# relay.net
KiCad netlist of a schematic drawn in Altium Designer
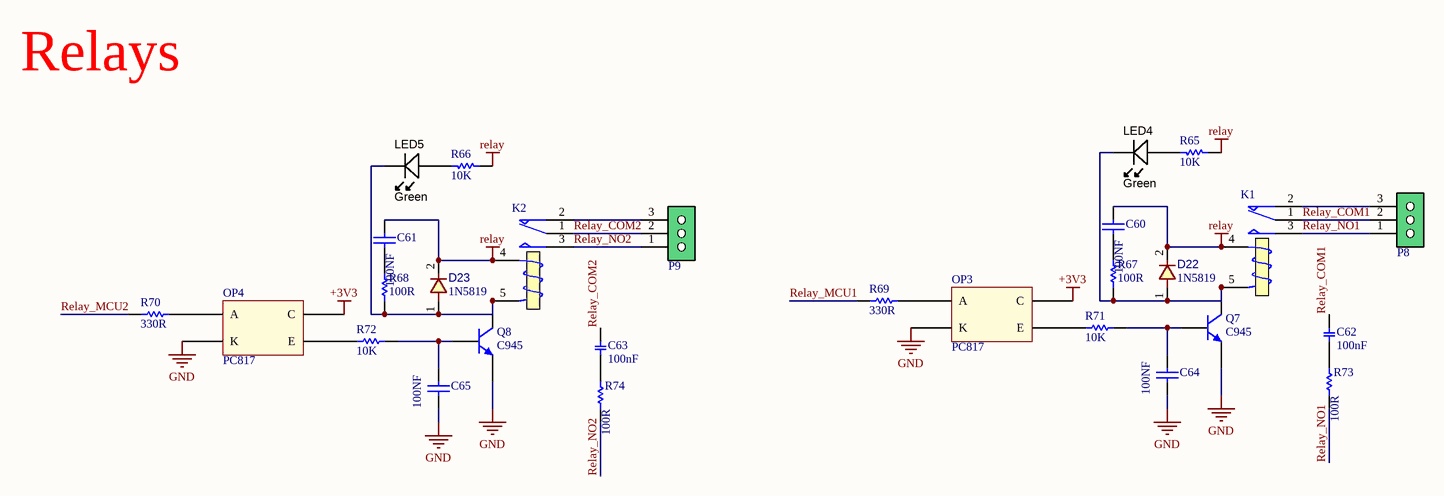
[diagram p0: relay.SchDoc]

(export (version "E")
  (design (tool "Eeschema 10.0.6"))
  (components
    (comp (ref "C60")
      (value "100NF")
      (footprint "CAP0603")
      (description "TOTAL CAPACITOR SMD PACK")
      (fields (field (name "DESIGNER") "Abbas Basereh"))
      (libsource (lib "Altium") (part "CAP SMD PACKAGE"))
    )
    (comp (ref "C61")
      (value "100NF")
      (footprint "CAP0603")
      (description "TOTAL CAPACITOR SMD PACK")
      (fields (field (name "DESIGNER") "Abbas Basereh"))
      (libsource (lib "Altium") (part "CAP SMD PACKAGE"))
    )
    (comp (ref "C62")
      (value "100nF")
      (footprint "Cap - 10nF - 630V")
      (description "Capacitor Polyester THD")
      (libsource (lib "Capacitor") (part "Capacitor Polyester THD"))
    )
    (comp (ref "C63")
      (value "100nF")
      (footprint "Cap - 10nF - 630V")
      (description "Capacitor Polyester THD")
      (libsource (lib "Capacitor") (part "Capacitor Polyester THD"))
    )
    (comp (ref "C64")
      (value "100NF")
      (footprint "CAP0603")
      (description "TOTAL CAPACITOR SMD PACK")
      (fields (field (name "DESIGNER") "Abbas Basereh"))
      (libsource (lib "Altium") (part "CAP SMD PACKAGE"))
    )
    (comp (ref "C65")
      (value "100NF")
      (footprint "CAP0603")
      (description "TOTAL CAPACITOR SMD PACK")
      (fields (field (name "DESIGNER") "Abbas Basereh"))
      (libsource (lib "Altium") (part "CAP SMD PACKAGE"))
    )
    (comp (ref "D22")
      (value "1N5819")
      (footprint "D_SMA")
      (description "DIODE, GENERAL PURPOSE, 1000V/1A")
      (fields (field (name "Comment") "1n5819 SMD SS31"))
      (libsource (lib "Diode") (part "1N4007 SMD M7"))
    )
    (comp (ref "D23")
      (value "1N5819")
      (footprint "D_SMA")
      (description "DIODE, GENERAL PURPOSE, 1000V/1A")
      (fields (field (name "Comment") "1n5819 SMD SS31"))
      (libsource (lib "Diode") (part "1N4007 SMD M7"))
    )
    (comp (ref "K1")
      (value "~")
      (footprint "Relay 18.85x15.35x15.70")
      (description "Single-Pole Dual-Throw Relay")
      (fields (field (name "DESIGNER") "Abbas Basereh"))
      (libsource (lib "2017AbbasBasereh9365731239 -ver1") (part "Relay_SPDT"))
    )
    (comp (ref "K2")
      (value "~")
      (footprint "Relay 18.85x15.35x15.70")
      (description "Single-Pole Dual-Throw Relay")
      (fields (field (name "DESIGNER") "Abbas Basereh"))
      (libsource (lib "2017AbbasBasereh9365731239 -ver1") (part "Relay_SPDT"))
    )
    (comp (ref "LED4")
      (value "Green")
      (footprint "LED-0603-GREEN")
      (description "LED 0603 SMD Green 570nm 50mcd 20mA")
      (libsource (lib "Utiliti_Library") (part "LED_SMD_Green_0603_570nm"))
    )
    (comp (ref "LED5")
      (value "Green")
      (footprint "LED-0603-GREEN")
      (description "LED 0603 SMD Green 570nm 50mcd 20mA")
      (libsource (lib "Utiliti_Library") (part "LED_SMD_Green_0603_570nm"))
    )
    (comp (ref "OP3")
      (value "PC817")
      (footprint "PC817 SMD")
      (description "PC817 optocpler")
      (libsource (lib "IC") (part "PC817"))
    )
    (comp (ref "OP4")
      (value "PC817")
      (footprint "PC817 SMD")
      (description "PC817 optocpler")
      (libsource (lib "IC") (part "PC817"))
    )
    (comp (ref "P8")
      (value "Phoenix 3")
      (footprint "PRKR3A")
      (libsource (lib "Connector") (part "Phoenix 3"))
    )
    (comp (ref "P9")
      (value "Phoenix 3")
      (footprint "PRKR3A")
      (libsource (lib "Connector") (part "Phoenix 3"))
    )
    (comp (ref "Q7")
      (value "C945")
      (footprint "SOT23_N")
      (description "NPN Silicon Epitaxial Planar Transistor")
      (fields (field (name "PUBLISHER") "Abbas Basereh"))
      (libsource (lib "2017AbbasBasereh9365731239 -ver1") (part "C945"))
    )
    (comp (ref "Q8")
      (value "C945")
      (footprint "SOT23_N")
      (description "NPN Silicon Epitaxial Planar Transistor")
      (fields (field (name "PUBLISHER") "Abbas Basereh"))
      (libsource (lib "2017AbbasBasereh9365731239 -ver1") (part "C945"))
    )
    (comp (ref "R65")
      (value "10K")
      (footprint "R0603")
      (description "Resistor SMD 0603")
      (libsource (lib "Resistor") (part "Resistor SMD 0603"))
    )
    (comp (ref "R66")
      (value "10K")
      (footprint "R0603")
      (description "Resistor SMD 0603")
      (libsource (lib "Resistor") (part "Resistor SMD 0603"))
    )
    (comp (ref "R67")
      (value "100R")
      (footprint "R0603")
      (description "Resistor SMD 0603")
      (libsource (lib "Resistor") (part "Resistor SMD 0603"))
    )
    (comp (ref "R68")
      (value "100R")
      (footprint "R0603")
      (description "Resistor SMD 0603")
      (libsource (lib "Resistor") (part "Resistor SMD 0603"))
    )
    (comp (ref "R69")
      (value "330R")
      (footprint "R0603")
      (description "Resistor SMD 0603")
      (libsource (lib "Resistor") (part "Resistor SMD 0603"))
    )
    (comp (ref "R70")
      (value "330R")
      (footprint "R0603")
      (description "Resistor SMD 0603")
      (libsource (lib "Resistor") (part "Resistor SMD 0603"))
    )
    (comp (ref "R71")
      (value "10K")
      (footprint "R0603")
      (description "Resistor SMD 0603")
      (libsource (lib "Resistor") (part "Resistor SMD 0603"))
    )
    (comp (ref "R72")
      (value "10K")
      (footprint "R0603")
      (description "Resistor SMD 0603")
      (libsource (lib "Resistor") (part "Resistor SMD 0603"))
    )
    (comp (ref "R73")
      (value "100R")
      (footprint "SMD-2512-RES")
      (description "Resistor SMD 2512")
      (libsource (lib "Resistor") (part "Resistor SMD 2512"))
    )
    (comp (ref "R74")
      (value "100R")
      (footprint "SMD-2512-RES")
      (description "Resistor SMD 2512")
      (libsource (lib "Resistor") (part "Resistor SMD 2512"))
    )
  )
  (nets
    (net (code "1") (name "+3V3") (class "Default")
      (node (ref "OP3") (pin "4") (pinfunction "C_4") (pintype "passive"))
      (node (ref "OP4") (pin "4") (pinfunction "C_4") (pintype "passive"))
    )
    (net (code "2") (name "/Relay_COM1") (class "Default")
      (node (ref "C62") (pin "2") (pinfunction "2_2") (pintype "passive"))
      (node (ref "K1") (pin "1") (pinfunction "COM_1") (pintype "passive"))
      (node (ref "P8") (pin "2") (pinfunction "2_2") (pintype "passive"))
    )
    (net (code "3") (name "/Relay_COM2") (class "Default")
      (node (ref "C63") (pin "2") (pinfunction "2_2") (pintype "passive"))
      (node (ref "K2") (pin "1") (pinfunction "COM_1") (pintype "passive"))
      (node (ref "P9") (pin "2") (pinfunction "2_2") (pintype "passive"))
    )
    (net (code "4") (name "/Relay_MCU1") (class "Default")
      (node (ref "R69") (pin "1") (pinfunction "1_1") (pintype "passive"))
    )
    (net (code "5") (name "/Relay_MCU2") (class "Default")
      (node (ref "R70") (pin "1") (pinfunction "1_1") (pintype "passive"))
    )
    (net (code "6") (name "/Relay_NO1") (class "Default")
      (node (ref "K1") (pin "3") (pinfunction "NO_3") (pintype "passive"))
      (node (ref "P8") (pin "1") (pinfunction "1_1") (pintype "passive"))
      (node (ref "R73") (pin "1") (pinfunction "1_1") (pintype "passive"))
    )
    (net (code "7") (name "/Relay_NO2") (class "Default")
      (node (ref "K2") (pin "3") (pinfunction "NO_3") (pintype "passive"))
      (node (ref "P9") (pin "1") (pinfunction "1_1") (pintype "passive"))
      (node (ref "R74") (pin "1") (pinfunction "1_1") (pintype "passive"))
    )
    (net (code "8") (name "GND") (class "Default")
      (node (ref "C64") (pin "1") (pinfunction "1_1") (pintype "passive"))
      (node (ref "C65") (pin "1") (pinfunction "1_1") (pintype "passive"))
      (node (ref "OP3") (pin "2") (pinfunction "K_2") (pintype "passive"))
      (node (ref "OP4") (pin "2") (pinfunction "K_2") (pintype "passive"))
      (node (ref "Q7") (pin "2") (pinfunction "E_2") (pintype "passive"))
      (node (ref "Q8") (pin "2") (pinfunction "E_2") (pintype "passive"))
    )
    (net (code "9") (name "Net-(C60-Pad1)") (class "Default")
      (node (ref "C60") (pin "1") (pinfunction "1_1") (pintype "passive"))
      (node (ref "R67") (pin "1") (pinfunction "1_1") (pintype "passive"))
    )
    (net (code "10") (name "Net-(C61-Pad1)") (class "Default")
      (node (ref "C61") (pin "1") (pinfunction "1_1") (pintype "passive"))
      (node (ref "R68") (pin "1") (pinfunction "1_1") (pintype "passive"))
    )
    (net (code "11") (name "Net-(C62-Pad1)") (class "Default")
      (node (ref "C62") (pin "1") (pinfunction "1_1") (pintype "passive"))
      (node (ref "R73") (pin "2") (pinfunction "2_2") (pintype "passive"))
    )
    (net (code "12") (name "Net-(C63-Pad1)") (class "Default")
      (node (ref "C63") (pin "1") (pinfunction "1_1") (pintype "passive"))
      (node (ref "R74") (pin "2") (pinfunction "2_2") (pintype "passive"))
    )
    (net (code "13") (name "Net-(K1-NC)") (class "Default")
      (node (ref "K1") (pin "2") (pinfunction "NC_2") (pintype "passive"))
      (node (ref "P8") (pin "3") (pinfunction "3_3") (pintype "passive"))
    )
    (net (code "14") (name "Net-(K1-T2)") (class "Default")
      (node (ref "D22") (pin "1") (pinfunction "1_1") (pintype "passive"))
      (node (ref "K1") (pin "5") (pinfunction "T2_5") (pintype "passive"))
      (node (ref "LED4") (pin "K") (pinfunction "K_K") (pintype "passive"))
      (node (ref "Q7") (pin "3") (pinfunction "C_3") (pintype "passive"))
      (node (ref "R67") (pin "2") (pinfunction "2_2") (pintype "passive"))
    )
    (net (code "15") (name "Net-(K2-NC)") (class "Default")
      (node (ref "K2") (pin "2") (pinfunction "NC_2") (pintype "passive"))
      (node (ref "P9") (pin "3") (pinfunction "3_3") (pintype "passive"))
    )
    (net (code "16") (name "Net-(K2-T2)") (class "Default")
      (node (ref "D23") (pin "1") (pinfunction "1_1") (pintype "passive"))
      (node (ref "K2") (pin "5") (pinfunction "T2_5") (pintype "passive"))
      (node (ref "LED5") (pin "K") (pinfunction "K_K") (pintype "passive"))
      (node (ref "Q8") (pin "3") (pinfunction "C_3") (pintype "passive"))
      (node (ref "R68") (pin "2") (pinfunction "2_2") (pintype "passive"))
    )
    (net (code "17") (name "Net-(LED4-PadA)") (class "Default")
      (node (ref "LED4") (pin "A") (pinfunction "A_A") (pintype "passive"))
      (node (ref "R65") (pin "1") (pinfunction "1_1") (pintype "passive"))
    )
    (net (code "18") (name "Net-(LED5-PadA)") (class "Default")
      (node (ref "LED5") (pin "A") (pinfunction "A_A") (pintype "passive"))
      (node (ref "R66") (pin "1") (pinfunction "1_1") (pintype "passive"))
    )
    (net (code "19") (name "Net-(OP3-A)") (class "Default")
      (node (ref "OP3") (pin "1") (pinfunction "A_1") (pintype "passive"))
      (node (ref "R69") (pin "2") (pinfunction "2_2") (pintype "passive"))
    )
    (net (code "20") (name "Net-(OP3-E)") (class "Default")
      (node (ref "OP3") (pin "3") (pinfunction "E_3") (pintype "passive"))
      (node (ref "R71") (pin "2") (pinfunction "2_2") (pintype "passive"))
    )
    (net (code "21") (name "Net-(OP4-A)") (class "Default")
      (node (ref "OP4") (pin "1") (pinfunction "A_1") (pintype "passive"))
      (node (ref "R70") (pin "2") (pinfunction "2_2") (pintype "passive"))
    )
    (net (code "22") (name "Net-(OP4-E)") (class "Default")
      (node (ref "OP4") (pin "3") (pinfunction "E_3") (pintype "passive"))
      (node (ref "R72") (pin "2") (pinfunction "2_2") (pintype "passive"))
    )
    (net (code "23") (name "Net-(Q7-B)") (class "Default")
      (node (ref "C64") (pin "2") (pinfunction "2_2") (pintype "passive"))
      (node (ref "Q7") (pin "1") (pinfunction "B_1") (pintype "passive"))
      (node (ref "R71") (pin "1") (pinfunction "1_1") (pintype "passive"))
    )
    (net (code "24") (name "Net-(Q8-B)") (class "Default")
      (node (ref "C65") (pin "2") (pinfunction "2_2") (pintype "passive"))
      (node (ref "Q8") (pin "1") (pinfunction "B_1") (pintype "passive"))
      (node (ref "R72") (pin "1") (pinfunction "1_1") (pintype "passive"))
    )
    (net (code "25") (name "relay") (class "Default")
      (node (ref "C60") (pin "2") (pinfunction "2_2") (pintype "passive"))
      (node (ref "C61") (pin "2") (pinfunction "2_2") (pintype "passive"))
      (node (ref "D22") (pin "2") (pinfunction "2_2") (pintype "passive"))
      (node (ref "D23") (pin "2") (pinfunction "2_2") (pintype "passive"))
      (node (ref "K1") (pin "4") (pinfunction "T1_4") (pintype "passive"))
      (node (ref "K2") (pin "4") (pinfunction "T1_4") (pintype "passive"))
      (node (ref "R65") (pin "2") (pinfunction "2_2") (pintype "passive"))
      (node (ref "R66") (pin "2") (pinfunction "2_2") (pintype "passive"))
    )
  )
)
